# Converter2.net
KiCad netlist of a schematic drawn in Altium Designer
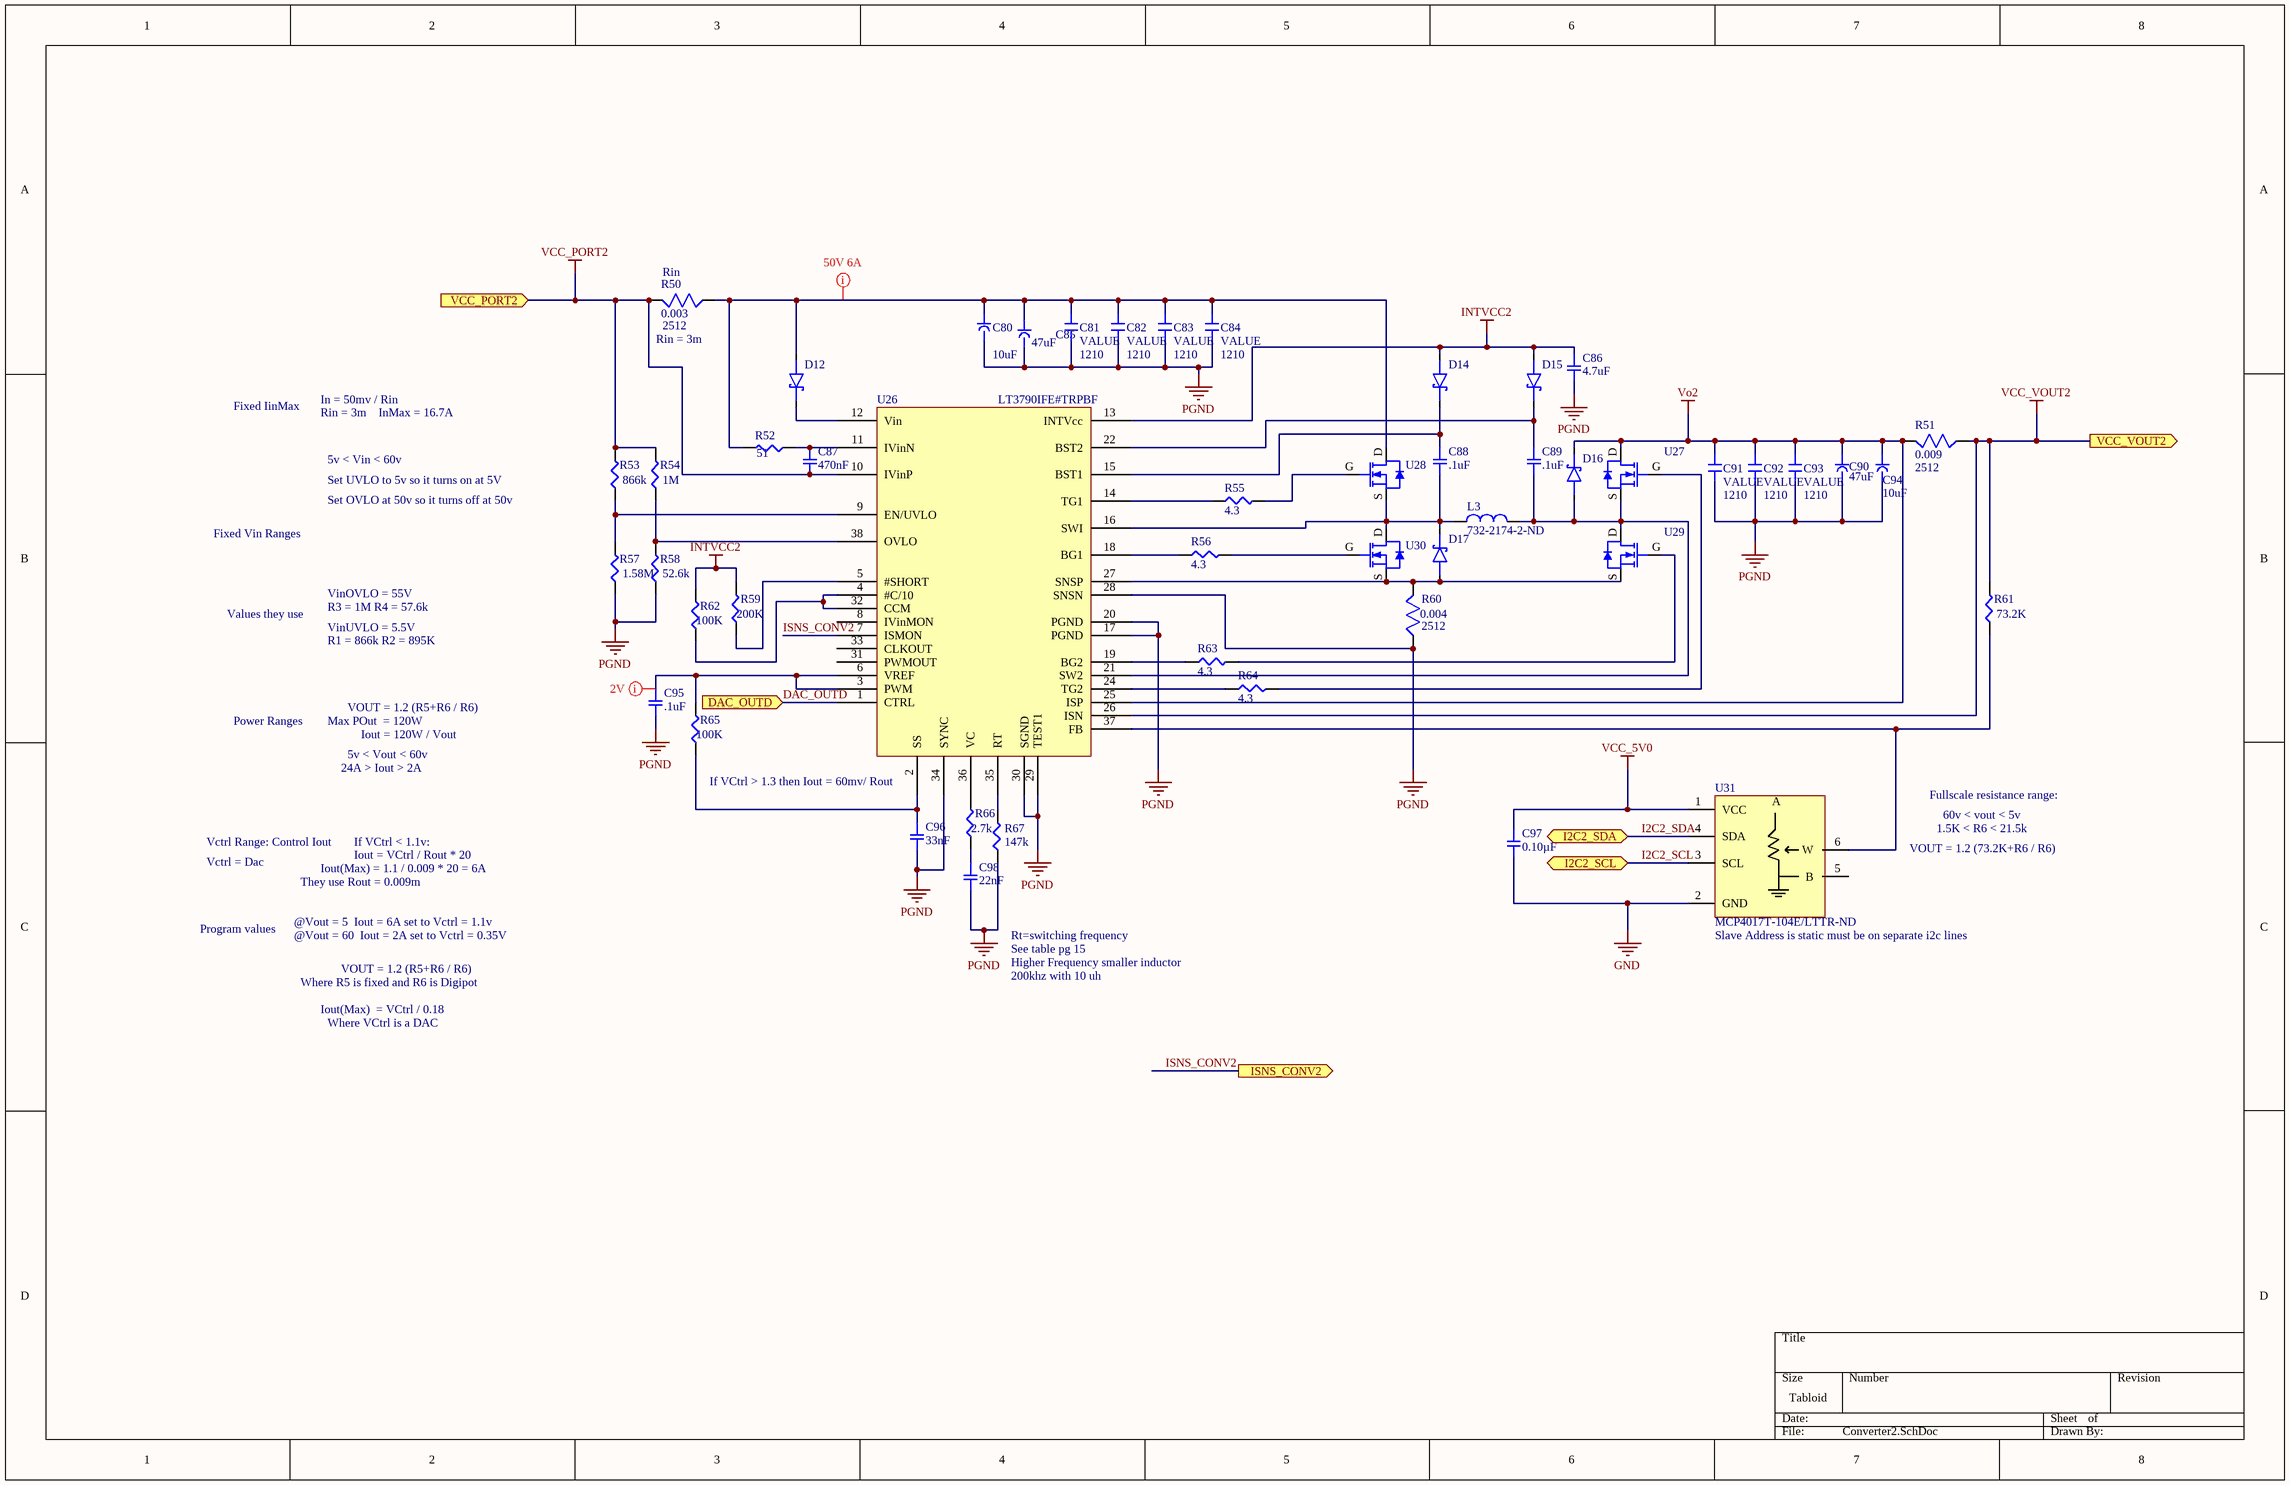
[diagram p0: Converter2.SchDoc]

(export (version "E")
  (design (tool "Eeschema 10.0.6"))
  (components
    (comp (ref "C80")
      (value "10uF")
      (footprint "panasonic d8")
      (description "CAP ALUM 10UF 20% 80V SMD")
      (fields (field (name "Comment") "EEE-FN1K100XL"))
      (libsource (lib "UniversalConverter_Symbols") (part "CAP ALUM 10UF"))
    )
    (comp (ref "C81")
      (value "VALUE")
      (footprint "1210 cap")
      (description "CAP SMD 1210")
      (fields (field (name "SIZE") "1210"))
      (libsource (lib "UniversalConverter_Symbols") (part "CAP SMD 1210"))
    )
    (comp (ref "C82")
      (value "VALUE")
      (footprint "1210 cap")
      (description "CAP SMD 1210")
      (fields (field (name "SIZE") "1210"))
      (libsource (lib "UniversalConverter_Symbols") (part "CAP SMD 1210"))
    )
    (comp (ref "C83")
      (value "VALUE")
      (footprint "1210 cap")
      (description "CAP SMD 1210")
      (fields (field (name "SIZE") "1210"))
      (libsource (lib "UniversalConverter_Symbols") (part "CAP SMD 1210"))
    )
    (comp (ref "C84")
      (value "VALUE")
      (footprint "1210 cap")
      (description "CAP SMD 1210")
      (fields (field (name "SIZE") "1210"))
      (libsource (lib "UniversalConverter_Symbols") (part "CAP SMD 1210"))
    )
    (comp (ref "C85")
      (value "10-EEE-FN1K470UVTR-ND")
      (footprint "EEE-FN1K470UV")
      (description "CAP ALUM 47UF 20% 80V SMD")
      (libsource (lib "UniversalConverter_Symbols") (part "CAP ALUM 47UF"))
    )
    (comp (ref "C86")
      (value "4.7uF")
      (footprint "SMD-0603C")
      (description "0603")
      (fields
        (field (name "DIGI-KEY PART NUMBER") "490-5764-1-ND")
        (field (name "PART NUMBER") "GCJ188R71H472KA01D")
      )
      (libsource (lib "capacitor_murata_0603") (part "GCJ188R71H472KA01D"))
    )
    (comp (ref "C87")
      (value "470nF")
      (footprint "SMD-0603C")
      (description "0603")
      (fields
        (field (name "DIGI-KEY PART NUMBER") "490-5764-1-ND")
        (field (name "PART NUMBER") "GCJ188R71H472KA01D")
      )
      (libsource (lib "capacitor_murata_0603") (part "GCJ188R71H472KA01D"))
    )
    (comp (ref "C88")
      (value ".1uF")
      (footprint "SMD-0603C")
      (description "0603")
      (fields
        (field (name "DIGI-KEY PART NUMBER") "490-5764-1-ND")
        (field (name "PART NUMBER") "GCJ188R71H472KA01D")
      )
      (libsource (lib "capacitor_murata_0603") (part "GCJ188R71H472KA01D"))
    )
    (comp (ref "C89")
      (value ".1uF")
      (footprint "SMD-0603C")
      (description "0603")
      (fields
        (field (name "DIGI-KEY PART NUMBER") "490-5764-1-ND")
        (field (name "PART NUMBER") "GCJ188R71H472KA01D")
      )
      (libsource (lib "capacitor_murata_0603") (part "GCJ188R71H472KA01D"))
    )
    (comp (ref "C90")
      (value "10-EEE-FN1K470UVTR-ND")
      (footprint "EEE-FN1K470UV")
      (description "CAP ALUM 47UF 20% 80V SMD")
      (libsource (lib "UniversalConverter_Symbols") (part "CAP ALUM 47UF"))
    )
    (comp (ref "C91")
      (value "VALUE")
      (footprint "1210 cap")
      (description "CAP SMD 1210")
      (fields (field (name "SIZE") "1210"))
      (libsource (lib "UniversalConverter_Symbols") (part "CAP SMD 1210"))
    )
    (comp (ref "C92")
      (value "VALUE")
      (footprint "1210 cap")
      (description "CAP SMD 1210")
      (fields (field (name "SIZE") "1210"))
      (libsource (lib "UniversalConverter_Symbols") (part "CAP SMD 1210"))
    )
    (comp (ref "C93")
      (value "VALUE")
      (footprint "1210 cap")
      (description "CAP SMD 1210")
      (fields (field (name "SIZE") "1210"))
      (libsource (lib "UniversalConverter_Symbols") (part "CAP SMD 1210"))
    )
    (comp (ref "C94")
      (value "10uF")
      (footprint "panasonic d8")
      (description "CAP ALUM 10UF 20% 80V SMD")
      (fields (field (name "Comment") "EEE-FN1K100XL"))
      (libsource (lib "UniversalConverter_Symbols") (part "CAP ALUM 10UF"))
    )
    (comp (ref "C95")
      (value ".1uF")
      (footprint "SMD-0603C")
      (description "0603")
      (fields
        (field (name "DIGI-KEY PART NUMBER") "490-5764-1-ND")
        (field (name "PART NUMBER") "GCJ188R71H472KA01D")
      )
      (libsource (lib "capacitor_murata_0603") (part "GCJ188R71H472KA01D"))
    )
    (comp (ref "C96")
      (value "33nF")
      (footprint "SMD-0603C")
      (description "0603")
      (fields
        (field (name "DIGI-KEY PART NUMBER") "490-5764-1-ND")
        (field (name "PART NUMBER") "GCJ188R71H472KA01D")
      )
      (libsource (lib "capacitor_murata_0603") (part "GCJ188R71H472KA01D"))
    )
    (comp (ref "C97")
      (value "0.10µF")
      (footprint "SMD-0603C")
      (description "CAP CER 0.1UF 50V X7R 0603")
      (fields
        (field (name "DIGI-KEY PART NUMBER") "490-5798-1-ND")
        (field (name "PART NUMBER") "GCJ188R71H104KA12D")
      )
      (libsource (lib "capacitor_murata_0603") (part "GCJ188R71H104KA12D"))
    )
    (comp (ref "C98")
      (value "22nF")
      (footprint "SMD-0603C")
      (description "0603")
      (fields
        (field (name "DIGI-KEY PART NUMBER") "490-5764-1-ND")
        (field (name "PART NUMBER") "GCJ188R71H472KA01D")
      )
      (libsource (lib "capacitor_murata_0603") (part "GCJ188R71H472KA01D"))
    )
    (comp (ref "D12")
      (value "SK58L-TPMSTR-ND")
      (footprint "SMC(DO-214AB)")
      (description "DIODE SCHOTTKY 80V 5A DO214AB/SMC\r\n\r\nDiode Schottky 80 V 5A Surface Mount SMC (DO-214AB)")
      (libsource (lib "UniversalConverter_Parts") (part "DIODE SK58L-TP"))
    )
    (comp (ref "D14")
      (value "BAT46WJ,115")
      (footprint "SOD323F")
      (description "DIODE SCHOTTKY 100V 250MA SOD323\r\n\r\nDiode Schottky 100 V 250mA (DC) Surface Mount SOD-323F")
      (fields (field (name "COPYRIGHT") "Copyright (C) 2021 Ultra Librarian. All rights reserved."))
      (libsource (lib "UniversalConverter_Symbols") (part "BAT46WJ,115"))
    )
    (comp (ref "D15")
      (value "BAT46WJ,115")
      (footprint "SOD323F")
      (description "DIODE SCHOTTKY 100V 250MA SOD323\r\n\r\nDiode Schottky 100 V 250mA (DC) Surface Mount SOD-323F")
      (fields (field (name "COPYRIGHT") "Copyright (C) 2021 Ultra Librarian. All rights reserved."))
      (libsource (lib "UniversalConverter_Symbols") (part "BAT46WJ,115"))
    )
    (comp (ref "D16")
      (value "SK58L-TPMSTR-ND")
      (footprint "SMC(DO-214AB)")
      (description "DIODE SCHOTTKY 80V 5A DO214AB/SMC\r\n\r\nDiode Schottky 80 V 5A Surface Mount SMC (DO-214AB)")
      (libsource (lib "UniversalConverter_Parts") (part "DIODE SK58L-TP"))
    )
    (comp (ref "D17")
      (value "SK58L-TPMSTR-ND")
      (footprint "SMC(DO-214AB)")
      (description "DIODE SCHOTTKY 80V 5A DO214AB/SMC\r\n\r\nDiode Schottky 80 V 5A Surface Mount SMC (DO-214AB)")
      (libsource (lib "UniversalConverter_Parts") (part "DIODE SK58L-TP"))
    )
    (comp (ref "L3")
      (value "732-2174-2-ND")
      (footprint "Inductor")
      (description "FIXED IND 6.8UH 18.5A 4.1MOHM SM")
      (libsource (lib "UniversalConverter_Parts") (part "INDUCTOR 7443556680"))
    )
    (comp (ref "R50")
      (value "0.003")
      (footprint "2512")
      (description "RES SMD 2512 2W")
      (fields (field (name "SIZE") "2512"))
      (libsource (lib "UniversalConverter_Symbols") (part "RES SMD 2512"))
    )
    (comp (ref "R51")
      (value "0.009")
      (footprint "2512")
      (description "RES SMD 2512 2W")
      (fields (field (name "SIZE") "2512"))
      (libsource (lib "UniversalConverter_Symbols") (part "RES SMD 2512"))
    )
    (comp (ref "R52")
      (value "51")
      (footprint "SMD-0603-RES")
      (description "0603")
      (fields (field (name "PART NUMBER") "ERJ-3BQJ5R6V") (field (name "DIGI-KEY PART NUMBER") "P17425CT-ND"))
      (libsource (lib "Panasonic_ERJ_0603") (part "ERJ-3BQJ5R6V"))
    )
    (comp (ref "R53")
      (value "866k")
      (footprint "SMD-0603-RES")
      (description "0603")
      (fields (field (name "PART NUMBER") "ERJ-3BQJ5R6V") (field (name "DIGI-KEY PART NUMBER") "P17425CT-ND"))
      (libsource (lib "Panasonic_ERJ_0603") (part "ERJ-3BQJ5R6V"))
    )
    (comp (ref "R54")
      (value "1M")
      (footprint "SMD-0603-RES")
      (description "0603")
      (fields (field (name "PART NUMBER") "ERJ-3BQJ5R6V") (field (name "DIGI-KEY PART NUMBER") "P17425CT-ND"))
      (libsource (lib "Panasonic_ERJ_0603") (part "ERJ-3BQJ5R6V"))
    )
    (comp (ref "R55")
      (value "4.3")
      (footprint "SMD-0603-RES")
      (description "RES SMD 1 OHM 1% 1/4W 0603")
      (fields (field (name "PART NUMBER") "ERJ-3BQF1R0V") (field (name "DIGI-KEY PART NUMBER") "P17371CT-ND"))
      (libsource (lib "Panasonic_ERJ_0603") (part "ERJ-3BQF1R0V"))
    )
    (comp (ref "R56")
      (value "4.3")
      (footprint "SMD-0603-RES")
      (description "RES SMD 1 OHM 1% 1/4W 0603")
      (fields (field (name "PART NUMBER") "ERJ-3BQF1R0V") (field (name "DIGI-KEY PART NUMBER") "P17371CT-ND"))
      (libsource (lib "Panasonic_ERJ_0603") (part "ERJ-3BQF1R0V"))
    )
    (comp (ref "R57")
      (value "1.58M")
      (footprint "SMD-0603-RES")
      (description "0603")
      (fields (field (name "PART NUMBER") "ERJ-3BQJ5R6V") (field (name "DIGI-KEY PART NUMBER") "P17425CT-ND"))
      (libsource (lib "Panasonic_ERJ_0603") (part "ERJ-3BQJ5R6V"))
    )
    (comp (ref "R58")
      (value "52.6k")
      (footprint "SMD-0603-RES")
      (description "0603")
      (fields (field (name "PART NUMBER") "ERJ-3BQJ5R6V") (field (name "DIGI-KEY PART NUMBER") "P17425CT-ND"))
      (libsource (lib "Panasonic_ERJ_0603") (part "ERJ-3BQJ5R6V"))
    )
    (comp (ref "R59")
      (value "200K")
      (footprint "SMD-0603-RES")
      (description "0603")
      (fields (field (name "PART NUMBER") "ERJ-3BQJ5R6V") (field (name "DIGI-KEY PART NUMBER") "P17425CT-ND"))
      (libsource (lib "Panasonic_ERJ_0603") (part "ERJ-3BQJ5R6V"))
    )
    (comp (ref "R60")
      (value "0.004")
      (footprint "2512")
      (description "RES SMD 2512 2W")
      (fields (field (name "SIZE") "2512"))
      (libsource (lib "UniversalConverter_Symbols") (part "RES SMD 2512"))
    )
    (comp (ref "R61")
      (value "73.2K")
      (footprint "SMD-0603-RES")
      (description "0603")
      (fields (field (name "PART NUMBER") "ERJ-3BQJ5R6V") (field (name "DIGI-KEY PART NUMBER") "P17425CT-ND"))
      (libsource (lib "Panasonic_ERJ_0603") (part "ERJ-3BQJ5R6V"))
    )
    (comp (ref "R62")
      (value "100K")
      (footprint "SMD-0603-RES")
      (description "0603")
      (fields (field (name "PART NUMBER") "ERJ-3BQJ5R6V") (field (name "DIGI-KEY PART NUMBER") "P17425CT-ND"))
      (libsource (lib "Panasonic_ERJ_0603") (part "ERJ-3BQJ5R6V"))
    )
    (comp (ref "R63")
      (value "4.3")
      (footprint "SMD-0603-RES")
      (description "RES SMD 1 OHM 1% 1/4W 0603")
      (fields (field (name "PART NUMBER") "ERJ-3BQF1R0V") (field (name "DIGI-KEY PART NUMBER") "P17371CT-ND"))
      (libsource (lib "Panasonic_ERJ_0603") (part "ERJ-3BQF1R0V"))
    )
    (comp (ref "R64")
      (value "4.3")
      (footprint "SMD-0603-RES")
      (description "RES SMD 1 OHM 1% 1/4W 0603")
      (fields (field (name "PART NUMBER") "ERJ-3BQF1R0V") (field (name "DIGI-KEY PART NUMBER") "P17371CT-ND"))
      (libsource (lib "Panasonic_ERJ_0603") (part "ERJ-3BQF1R0V"))
    )
    (comp (ref "R65")
      (value "100K")
      (footprint "SMD-0603-RES")
      (description "0603")
      (fields (field (name "PART NUMBER") "ERJ-3BQJ5R6V") (field (name "DIGI-KEY PART NUMBER") "P17425CT-ND"))
      (libsource (lib "Panasonic_ERJ_0603") (part "ERJ-3BQJ5R6V"))
    )
    (comp (ref "R66")
      (value "2.7k")
      (footprint "SMD-0603-RES")
      (description "0603")
      (fields (field (name "PART NUMBER") "ERJ-3BQJ5R6V") (field (name "DIGI-KEY PART NUMBER") "P17425CT-ND"))
      (libsource (lib "Panasonic_ERJ_0603") (part "ERJ-3BQJ5R6V"))
    )
    (comp (ref "R67")
      (value "147k")
      (footprint "SMD-0603-RES")
      (description "0603")
      (fields (field (name "PART NUMBER") "ERJ-3BQJ5R6V") (field (name "DIGI-KEY PART NUMBER") "P17425CT-ND"))
      (libsource (lib "Panasonic_ERJ_0603") (part "ERJ-3BQJ5R6V"))
    )
    (comp (ref "U26")
      (value "LT3790IFE#TRPBF")
      (footprint "TSSOP-38-GNDPAD")
      (libsource (lib "UniversalConverter_Parts") (part "IC LT3790 BUCK/BOOST 60V 150W"))
    )
    (comp (ref "U27")
      (value "SQJA80EP-T1_GE3TR-ND")
      (footprint "PowerPAK® SO-8L SINGLE")
      (description "MOSFET N-CH 80V 60A PPAK SO-8")
      (libsource (lib "UniversalConverter_Parts") (part "FET SQJA80EP-T1_GE3"))
    )
    (comp (ref "U28")
      (value "SQJA80EP-T1_GE3TR-ND")
      (footprint "PowerPAK® SO-8L SINGLE")
      (description "MOSFET N-CH 80V 60A PPAK SO-8")
      (libsource (lib "UniversalConverter_Parts") (part "FET SQJA80EP-T1_GE3"))
    )
    (comp (ref "U29")
      (value "SQJA80EP-T1_GE3TR-ND")
      (footprint "PowerPAK® SO-8L SINGLE")
      (description "MOSFET N-CH 80V 60A PPAK SO-8")
      (libsource (lib "UniversalConverter_Parts") (part "FET SQJA80EP-T1_GE3"))
    )
    (comp (ref "U30")
      (value "SQJA80EP-T1_GE3TR-ND")
      (footprint "PowerPAK® SO-8L SINGLE")
      (description "MOSFET N-CH 80V 60A PPAK SO-8")
      (libsource (lib "UniversalConverter_Parts") (part "FET SQJA80EP-T1_GE3"))
    )
    (comp (ref "U31")
      (value "MCP4017T-104E/LTTR-ND")
      (footprint "SC70")
      (description "IC DGT POT 100KOHM 128TAP SC70-6")
      (libsource (lib "UniversalConverter_Symbols") (part "IC DIGIPOT MCP4017T-104E/LT"))
    )
  )
  (nets
    (net (code "1") (name "/DAC_OUTD") (class "Default")
      (node (ref "U26") (pin "1") (pinfunction "CTRL_1") (pintype "passive"))
    )
    (net (code "2") (name "/I2C2_SCL") (class "Default")
      (node (ref "U31") (pin "3") (pinfunction "SCL_3") (pintype "passive"))
    )
    (net (code "3") (name "/I2C2_SDA") (class "Default")
      (node (ref "U31") (pin "4") (pinfunction "SDA_4") (pintype "passive"))
    )
    (net (code "4") (name "/ISNS_CONV2") (class "Default")
      (node (ref "U26") (pin "7") (pinfunction "ISMON_7") (pintype "passive"))
    )
    (net (code "5") (name "GND") (class "Default")
      (node (ref "C97") (pin "2") (pinfunction "2_2") (pintype "passive"))
      (node (ref "U31") (pin "2") (pinfunction "GND_2") (pintype "passive"))
    )
    (net (code "6") (name "INTVCC2") (class "Default")
      (node (ref "C86") (pin "1") (pinfunction "1_1") (pintype "passive"))
      (node (ref "D14") (pin "2") (pinfunction "2_2") (pintype "passive"))
      (node (ref "D15") (pin "2") (pinfunction "2_2") (pintype "passive"))
      (node (ref "R59") (pin "2") (pinfunction "2_2") (pintype "passive"))
      (node (ref "R62") (pin "2") (pinfunction "2_2") (pintype "passive"))
      (node (ref "U26") (pin "13") (pinfunction "INTVcc_13") (pintype "passive"))
    )
    (net (code "7") (name "Net-(C98-Pad1)") (class "Default")
      (node (ref "C98") (pin "1") (pinfunction "1_1") (pintype "passive"))
      (node (ref "R66") (pin "1") (pinfunction "1_1") (pintype "passive"))
    )
    (net (code "8") (name "Net-(U26-#C{slash}10)") (class "Default")
      (node (ref "R62") (pin "1") (pinfunction "1_1") (pintype "passive"))
      (node (ref "U26") (pin "32") (pinfunction "CCM_32") (pintype "passive"))
      (node (ref "U26") (pin "4") (pinfunction "#C/10_4") (pintype "passive"))
    )
    (net (code "9") (name "Net-(U26-#SHORT)") (class "Default")
      (node (ref "R59") (pin "1") (pinfunction "1_1") (pintype "passive"))
      (node (ref "U26") (pin "5") (pinfunction "#SHORT_5") (pintype "passive"))
    )
    (net (code "10") (name "Net-(U26-BG1)") (class "Default")
      (node (ref "R56") (pin "1") (pinfunction "1_1") (pintype "passive"))
      (node (ref "U26") (pin "18") (pinfunction "BG1_18") (pintype "passive"))
    )
    (net (code "11") (name "Net-(U26-BG2)") (class "Default")
      (node (ref "R63") (pin "1") (pinfunction "1_1") (pintype "passive"))
      (node (ref "U26") (pin "19") (pinfunction "BG2_19") (pintype "passive"))
    )
    (net (code "12") (name "Net-(U26-BST1)") (class "Default")
      (node (ref "C88") (pin "1") (pinfunction "1_1") (pintype "passive"))
      (node (ref "D14") (pin "1") (pinfunction "1_1") (pintype "passive"))
      (node (ref "U26") (pin "15") (pinfunction "BST1_15") (pintype "passive"))
    )
    (net (code "13") (name "Net-(U26-BST2)") (class "Default")
      (node (ref "C89") (pin "1") (pinfunction "1_1") (pintype "passive"))
      (node (ref "D15") (pin "1") (pinfunction "1_1") (pintype "passive"))
      (node (ref "U26") (pin "22") (pinfunction "BST2_22") (pintype "passive"))
    )
    (net (code "14") (name "Net-(U26-EN{slash}UVLO)") (class "Default")
      (node (ref "R53") (pin "1") (pinfunction "1_1") (pintype "passive"))
      (node (ref "R57") (pin "2") (pinfunction "2_2") (pintype "passive"))
      (node (ref "U26") (pin "9") (pinfunction "EN/UVLO_9") (pintype "passive"))
    )
    (net (code "15") (name "Net-(U26-FB)") (class "Default")
      (node (ref "R61") (pin "1") (pinfunction "1_1") (pintype "passive"))
      (node (ref "U26") (pin "37") (pinfunction "FB_37") (pintype "passive"))
      (node (ref "U31") (pin "6") (pinfunction "W_6") (pintype "passive"))
    )
    (net (code "16") (name "Net-(U26-IVinN)") (class "Default")
      (node (ref "C87") (pin "1") (pinfunction "1_1") (pintype "passive"))
      (node (ref "R52") (pin "1") (pinfunction "1_1") (pintype "passive"))
      (node (ref "U26") (pin "11") (pinfunction "IVinN_11") (pintype "passive"))
    )
    (net (code "17") (name "Net-(U26-OVLO)") (class "Default")
      (node (ref "R54") (pin "1") (pinfunction "1_1") (pintype "passive"))
      (node (ref "R58") (pin "2") (pinfunction "2_2") (pintype "passive"))
      (node (ref "U26") (pin "38") (pinfunction "OVLO_38") (pintype "passive"))
    )
    (net (code "18") (name "Net-(U26-PWM)") (class "Default")
      (node (ref "C95") (pin "1") (pinfunction "1_1") (pintype "passive"))
      (node (ref "R65") (pin "2") (pinfunction "2_2") (pintype "passive"))
      (node (ref "U26") (pin "3") (pinfunction "PWM_3") (pintype "passive"))
      (node (ref "U26") (pin "6") (pinfunction "VREF_6") (pintype "passive"))
    )
    (net (code "19") (name "Net-(U26-RT)") (class "Default")
      (node (ref "R67") (pin "2") (pinfunction "2_2") (pintype "passive"))
      (node (ref "U26") (pin "35") (pinfunction "RT_35") (pintype "passive"))
    )
    (net (code "20") (name "Net-(U26-SNSP)") (class "Default")
      (node (ref "D17") (pin "2") (pinfunction "2_2") (pintype "passive"))
      (node (ref "R60") (pin "2") (pinfunction "2_2") (pintype "passive"))
      (node (ref "U26") (pin "27") (pinfunction "SNSP_27") (pintype "passive"))
      (node (ref "U29") (pin "S") (pinfunction "SOURCE_S") (pintype "passive"))
      (node (ref "U30") (pin "S") (pinfunction "SOURCE_S") (pintype "passive"))
    )
    (net (code "21") (name "Net-(U26-SS)") (class "Default")
      (node (ref "C96") (pin "1") (pinfunction "1_1") (pintype "passive"))
      (node (ref "R65") (pin "1") (pinfunction "1_1") (pintype "passive"))
      (node (ref "U26") (pin "2") (pinfunction "SS_2") (pintype "passive"))
    )
    (net (code "22") (name "Net-(U26-SW2)") (class "Default")
      (node (ref "C89") (pin "2") (pinfunction "2_2") (pintype "passive"))
      (node (ref "D16") (pin "2") (pinfunction "2_2") (pintype "passive"))
      (node (ref "L3") (pin "2") (pinfunction "2_2") (pintype "passive"))
      (node (ref "U26") (pin "21") (pinfunction "SW2_21") (pintype "passive"))
      (node (ref "U27") (pin "S") (pinfunction "SOURCE_S") (pintype "passive"))
      (node (ref "U29") (pin "D") (pinfunction "DRAIN_D") (pintype "passive"))
    )
    (net (code "23") (name "Net-(U26-SWI)") (class "Default")
      (node (ref "C88") (pin "2") (pinfunction "2_2") (pintype "passive"))
      (node (ref "D17") (pin "1") (pinfunction "1_1") (pintype "passive"))
      (node (ref "L3") (pin "1") (pinfunction "1_1") (pintype "passive"))
      (node (ref "U26") (pin "16") (pinfunction "SWI_16") (pintype "passive"))
      (node (ref "U28") (pin "S") (pinfunction "SOURCE_S") (pintype "passive"))
      (node (ref "U30") (pin "D") (pinfunction "DRAIN_D") (pintype "passive"))
    )
    (net (code "24") (name "Net-(U26-TG1)") (class "Default")
      (node (ref "R55") (pin "1") (pinfunction "1_1") (pintype "passive"))
      (node (ref "U26") (pin "14") (pinfunction "TG1_14") (pintype "passive"))
    )
    (net (code "25") (name "Net-(U26-TG2)") (class "Default")
      (node (ref "R64") (pin "1") (pinfunction "1_1") (pintype "passive"))
      (node (ref "U26") (pin "24") (pinfunction "TG2_24") (pintype "passive"))
    )
    (net (code "26") (name "Net-(U26-VC)") (class "Default")
      (node (ref "R66") (pin "2") (pinfunction "2_2") (pintype "passive"))
      (node (ref "U26") (pin "36") (pinfunction "VC_36") (pintype "passive"))
    )
    (net (code "27") (name "Net-(U26-Vin)") (class "Default")
      (node (ref "D12") (pin "1") (pinfunction "1_1") (pintype "passive"))
      (node (ref "U26") (pin "12") (pinfunction "Vin_12") (pintype "passive"))
    )
    (net (code "28") (name "Net-(U27-GATE)") (class "Default")
      (node (ref "R64") (pin "2") (pinfunction "2_2") (pintype "passive"))
      (node (ref "U27") (pin "G") (pinfunction "GATE_G") (pintype "passive"))
    )
    (net (code "29") (name "Net-(U28-DRAIN)") (class "Default")
      (node (ref "C80") (pin "1") (pinfunction "1_1") (pintype "passive"))
      (node (ref "C81") (pin "1") (pinfunction "1_1") (pintype "passive"))
      (node (ref "C82") (pin "1") (pinfunction "1_1") (pintype "passive"))
      (node (ref "C83") (pin "1") (pinfunction "1_1") (pintype "passive"))
      (node (ref "C84") (pin "1") (pinfunction "1_1") (pintype "passive"))
      (node (ref "C85") (pin "2") (pinfunction "2_2") (pintype "passive"))
      (node (ref "D12") (pin "2") (pinfunction "2_2") (pintype "passive"))
      (node (ref "R50") (pin "1") (pinfunction "1_1") (pintype "passive"))
      (node (ref "R52") (pin "2") (pinfunction "2_2") (pintype "passive"))
      (node (ref "U28") (pin "D") (pinfunction "DRAIN_D") (pintype "passive"))
    )
    (net (code "30") (name "Net-(U28-GATE)") (class "Default")
      (node (ref "R55") (pin "2") (pinfunction "2_2") (pintype "passive"))
      (node (ref "U28") (pin "G") (pinfunction "GATE_G") (pintype "passive"))
    )
    (net (code "31") (name "Net-(U29-GATE)") (class "Default")
      (node (ref "R63") (pin "2") (pinfunction "2_2") (pintype "passive"))
      (node (ref "U29") (pin "G") (pinfunction "GATE_G") (pintype "passive"))
    )
    (net (code "32") (name "Net-(U30-GATE)") (class "Default")
      (node (ref "R56") (pin "2") (pinfunction "2_2") (pintype "passive"))
      (node (ref "U30") (pin "G") (pinfunction "GATE_G") (pintype "passive"))
    )
    (net (code "33") (name "PGND") (class "Default")
      (node (ref "C80") (pin "2") (pinfunction "2_2") (pintype "passive"))
      (node (ref "C81") (pin "2") (pinfunction "2_2") (pintype "passive"))
      (node (ref "C82") (pin "2") (pinfunction "2_2") (pintype "passive"))
      (node (ref "C83") (pin "2") (pinfunction "2_2") (pintype "passive"))
      (node (ref "C84") (pin "2") (pinfunction "2_2") (pintype "passive"))
      (node (ref "C85") (pin "1") (pinfunction "1_1") (pintype "passive"))
      (node (ref "C86") (pin "2") (pinfunction "2_2") (pintype "passive"))
      (node (ref "C90") (pin "1") (pinfunction "1_1") (pintype "passive"))
      (node (ref "C91") (pin "2") (pinfunction "2_2") (pintype "passive"))
      (node (ref "C92") (pin "2") (pinfunction "2_2") (pintype "passive"))
      (node (ref "C93") (pin "2") (pinfunction "2_2") (pintype "passive"))
      (node (ref "C94") (pin "2") (pinfunction "2_2") (pintype "passive"))
      (node (ref "C95") (pin "2") (pinfunction "2_2") (pintype "passive"))
      (node (ref "C96") (pin "2") (pinfunction "2_2") (pintype "passive"))
      (node (ref "C98") (pin "2") (pinfunction "2_2") (pintype "passive"))
      (node (ref "R57") (pin "1") (pinfunction "1_1") (pintype "passive"))
      (node (ref "R58") (pin "1") (pinfunction "1_1") (pintype "passive"))
      (node (ref "R60") (pin "1") (pinfunction "1_1") (pintype "passive"))
      (node (ref "R67") (pin "1") (pinfunction "1_1") (pintype "passive"))
      (node (ref "U26") (pin "17") (pinfunction "PGND_17") (pintype "passive"))
      (node (ref "U26") (pin "20") (pinfunction "PGND_20") (pintype "passive"))
      (node (ref "U26") (pin "28") (pinfunction "SNSN_28") (pintype "passive"))
      (node (ref "U26") (pin "29") (pinfunction "TEST1_29") (pintype "passive"))
      (node (ref "U26") (pin "30") (pinfunction "SGND_30") (pintype "passive"))
      (node (ref "U26") (pin "34") (pinfunction "SYNC_34") (pintype "passive"))
    )
    (net (code "34") (name "VCC_5V0") (class "Default")
      (node (ref "C97") (pin "1") (pinfunction "1_1") (pintype "passive"))
      (node (ref "U31") (pin "1") (pinfunction "VCC_1") (pintype "passive"))
    )
    (net (code "35") (name "VCC_PORT2") (class "Default")
      (node (ref "C87") (pin "2") (pinfunction "2_2") (pintype "passive"))
      (node (ref "R50") (pin "2") (pinfunction "2_2") (pintype "passive"))
      (node (ref "R53") (pin "2") (pinfunction "2_2") (pintype "passive"))
      (node (ref "R54") (pin "2") (pinfunction "2_2") (pintype "passive"))
      (node (ref "U26") (pin "10") (pinfunction "IVinP_10") (pintype "passive"))
    )
    (net (code "36") (name "VCC_VOUT2") (class "Default")
      (node (ref "R51") (pin "1") (pinfunction "1_1") (pintype "passive"))
      (node (ref "R61") (pin "2") (pinfunction "2_2") (pintype "passive"))
      (node (ref "U26") (pin "26") (pinfunction "ISN_26") (pintype "passive"))
    )
    (net (code "37") (name "Vo2") (class "Default")
      (node (ref "C90") (pin "2") (pinfunction "2_2") (pintype "passive"))
      (node (ref "C91") (pin "1") (pinfunction "1_1") (pintype "passive"))
      (node (ref "C92") (pin "1") (pinfunction "1_1") (pintype "passive"))
      (node (ref "C93") (pin "1") (pinfunction "1_1") (pintype "passive"))
      (node (ref "C94") (pin "1") (pinfunction "1_1") (pintype "passive"))
      (node (ref "D16") (pin "1") (pinfunction "1_1") (pintype "passive"))
      (node (ref "R51") (pin "2") (pinfunction "2_2") (pintype "passive"))
      (node (ref "U26") (pin "25") (pinfunction "ISP_25") (pintype "passive"))
      (node (ref "U27") (pin "D") (pinfunction "DRAIN_D") (pintype "passive"))
    )
    (net (code "38") (name "unconnected-(U26-CLKOUT-Pad33)") (class "Default")
      (node (ref "U26") (pin "33") (pinfunction "CLKOUT_33") (pintype "passive"))
    )
    (net (code "39") (name "unconnected-(U26-IVinMON-Pad8)") (class "Default")
      (node (ref "U26") (pin "8") (pinfunction "IVinMON_8") (pintype "passive"))
    )
    (net (code "40") (name "unconnected-(U26-PWMOUT-Pad31)") (class "Default")
      (node (ref "U26") (pin "31") (pinfunction "PWMOUT_31") (pintype "passive"))
    )
    (net (code "41") (name "unconnected-(U31-B-Pad5)") (class "Default")
      (node (ref "U31") (pin "5") (pinfunction "B_5") (pintype "passive"))
    )
  )
)
